# BLE_--_HM-10_--_Carduino_Breakout_v1_0_4.net
KiCad netlist of a schematic drawn in EAGLE
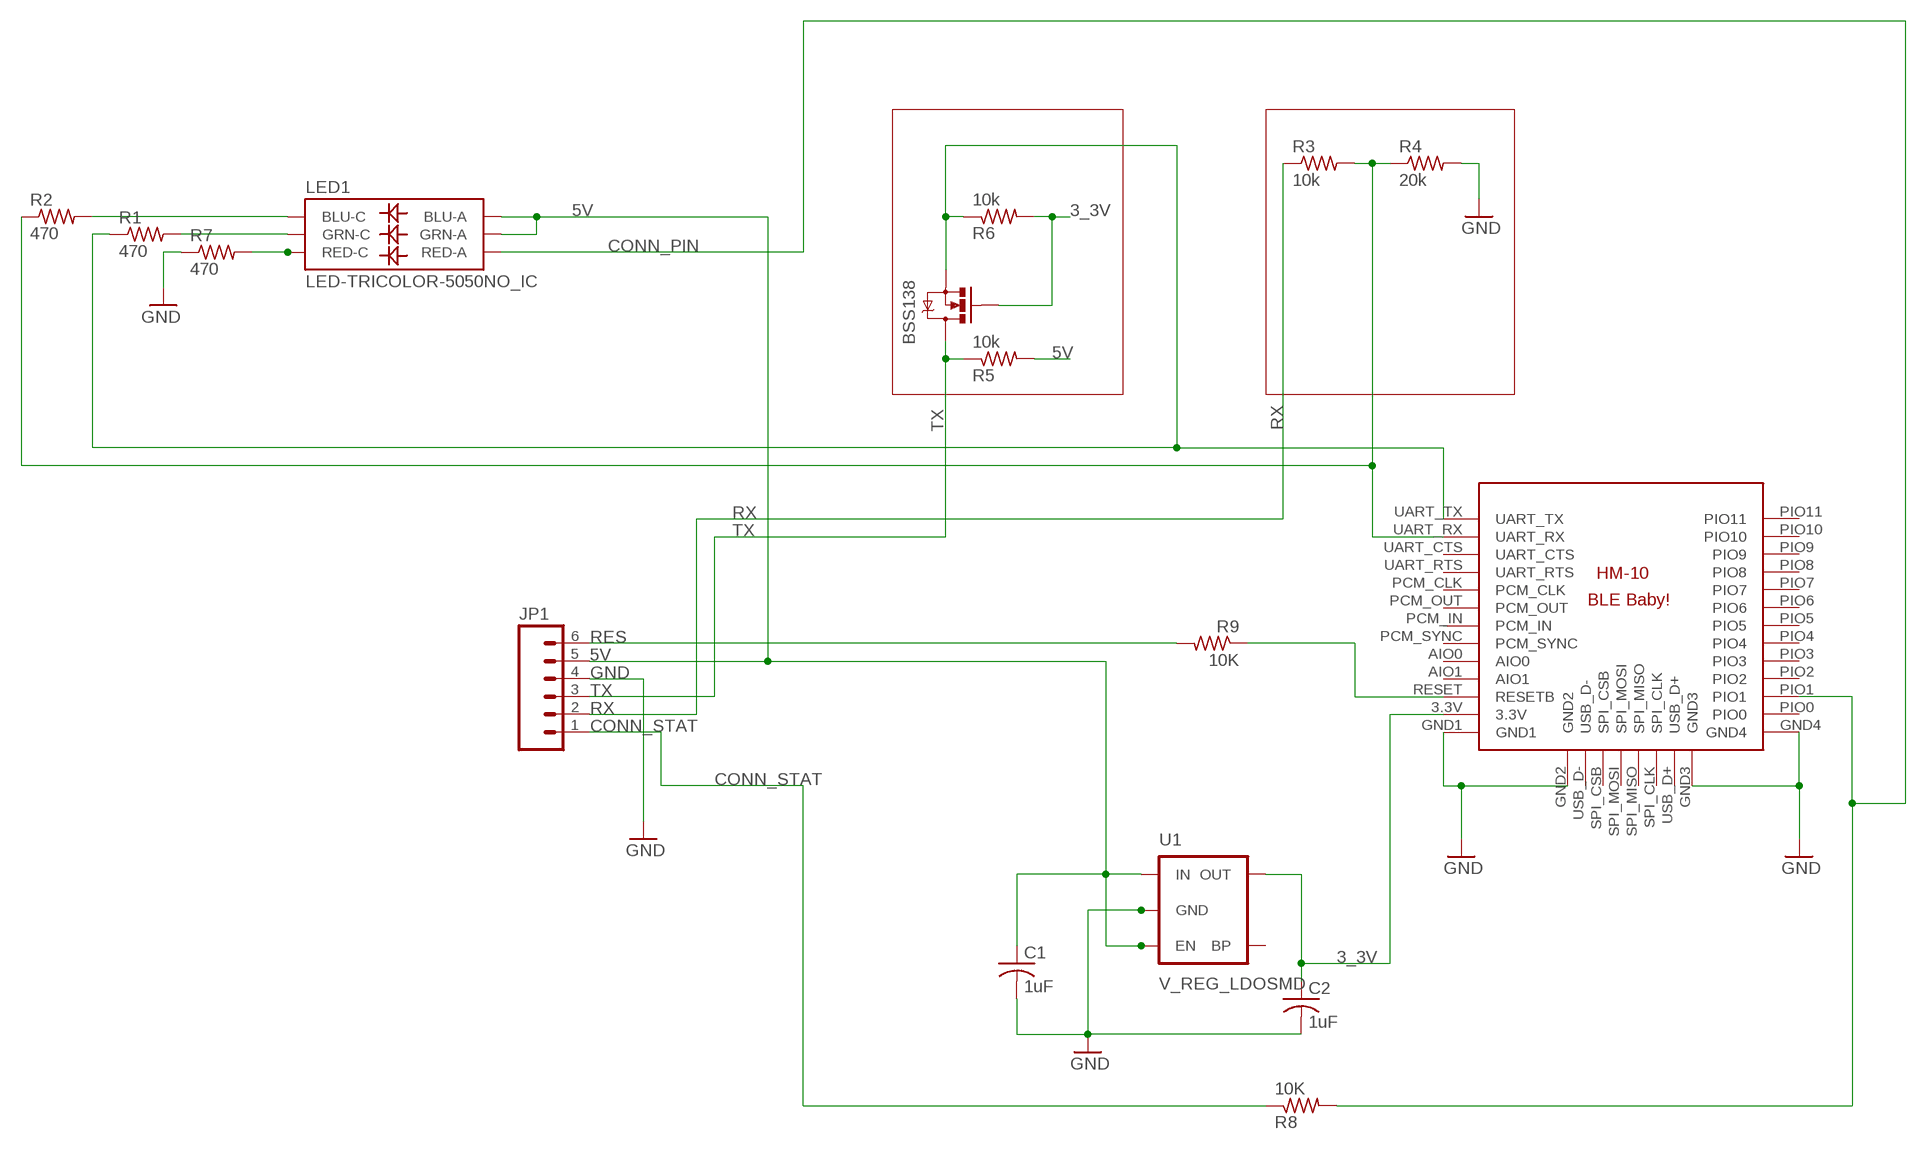
[diagram p0: schematic, sheet 1]

(export (version "E")
  (design (tool "Eeschema 10.0.6"))
  (components
    (comp (ref "BSS138")
      (value "MOSFET-NCHANNELSMD")
      (footprint "eagle-import:SOT23-3")
      (libsource (lib "eagle-import") (part "MOSFET-NCHANNELSMD"))
    )
    (comp (ref "C1")
      (value "1uF")
      (footprint "eagle-import:C0402")
      (libsource (lib "eagle-import") (part "C-USC0402"))
    )
    (comp (ref "C2")
      (value "1uF")
      (footprint "eagle-import:C0402")
      (libsource (lib "eagle-import") (part "C-USC0402"))
    )
    (comp (ref "JP1")
      (value "M06SIP")
      (footprint "eagle-import:1X06")
      (libsource (lib "eagle-import") (part "M06SIP"))
    )
    (comp (ref "LED1")
      (value "LED-TRICOLOR-5050NO_IC")
      (footprint "eagle-import:LED-TRICOLOR-5050")
      (libsource (lib "eagle-import") (part "LED-TRICOLOR-5050NO_IC"))
    )
    (comp (ref "R1")
      (value "470")
      (footprint "eagle-import:R0402")
      (libsource (lib "eagle-import") (part "R-US_R0402"))
    )
    (comp (ref "R2")
      (value "470")
      (footprint "eagle-import:R0402")
      (libsource (lib "eagle-import") (part "R-US_R0402"))
    )
    (comp (ref "R3")
      (value "10k")
      (footprint "eagle-import:R0402")
      (libsource (lib "eagle-import") (part "R-US_R0402"))
    )
    (comp (ref "R4")
      (value "20k")
      (footprint "eagle-import:R0402")
      (libsource (lib "eagle-import") (part "R-US_R0402"))
    )
    (comp (ref "R5")
      (value "10k")
      (footprint "eagle-import:R0402")
      (libsource (lib "eagle-import") (part "R-US_R0402"))
    )
    (comp (ref "R6")
      (value "10k")
      (footprint "eagle-import:R0402")
      (libsource (lib "eagle-import") (part "R-US_R0402"))
    )
    (comp (ref "R7")
      (value "470")
      (footprint "eagle-import:R0402")
      (libsource (lib "eagle-import") (part "R-US_R0402"))
    )
    (comp (ref "R8")
      (value "10K")
      (footprint "eagle-import:R0402")
      (libsource (lib "eagle-import") (part "R-US_R0402"))
    )
    (comp (ref "R9")
      (value "10K")
      (footprint "eagle-import:R0402")
      (libsource (lib "eagle-import") (part "R-US_R0402"))
    )
    (comp (ref "U$1")
      (value "BLE-HM-10")
      (footprint "eagle-import:BLE-HM-10")
      (libsource (lib "eagle-import") (part "BLE-HM-10"))
    )
    (comp (ref "U1")
      (value "V_REG_LDOSMD")
      (footprint "eagle-import:SOT23-5")
      (libsource (lib "eagle-import") (part "V_REG_LDOSMD"))
    )
  )
  (nets
    (net (code "1") (name "/3_3V") (class "Default")
      (node (ref "BSS138") (pin "1") (pinfunction "G_1") (pintype "passive"))
      (node (ref "C2") (pin "1") (pinfunction "1_1") (pintype "passive"))
      (node (ref "R6") (pin "2") (pinfunction "2_2") (pintype "passive"))
      (node (ref "U$1") (pin "3.3V") (pinfunction "3.3V_3.3V") (pintype "bidirectional"))
      (node (ref "U1") (pin "5") (pinfunction "OUT_5") (pintype "passive"))
    )
    (net (code "2") (name "/5V") (class "Default")
      (node (ref "C1") (pin "1") (pinfunction "1_1") (pintype "passive"))
      (node (ref "JP1") (pin "5") (pinfunction "5_5") (pintype "passive"))
      (node (ref "LED1") (pin "1") (pinfunction "GRN-A_1") (pintype "bidirectional"))
      (node (ref "LED1") (pin "3") (pinfunction "BLU-A_3") (pintype "bidirectional"))
      (node (ref "R5") (pin "2") (pinfunction "2_2") (pintype "passive"))
      (node (ref "U1") (pin "1") (pinfunction "IN_1") (pintype "input"))
      (node (ref "U1") (pin "3") (pinfunction "EN_3") (pintype "input"))
    )
    (net (code "3") (name "/CONN_PIN") (class "Default")
      (node (ref "LED1") (pin "2") (pinfunction "RED-A_2") (pintype "bidirectional"))
      (node (ref "R8") (pin "2") (pinfunction "2_2") (pintype "passive"))
      (node (ref "U$1") (pin "PIO1") (pinfunction "PIO1_PIO1") (pintype "bidirectional"))
    )
    (net (code "4") (name "/CONN_STAT") (class "Default")
      (node (ref "JP1") (pin "1") (pinfunction "1_1") (pintype "passive"))
      (node (ref "R8") (pin "1") (pinfunction "1_1") (pintype "passive"))
    )
    (net (code "5") (name "/RES") (class "Default")
      (node (ref "R9") (pin "1") (pinfunction "1_1") (pintype "passive"))
      (node (ref "U$1") (pin "RESET") (pinfunction "RESETB_RESET") (pintype "bidirectional"))
    )
    (net (code "6") (name "/RX") (class "Default")
      (node (ref "JP1") (pin "2") (pinfunction "2_2") (pintype "passive"))
      (node (ref "R3") (pin "1") (pinfunction "1_1") (pintype "passive"))
    )
    (net (code "7") (name "/TX") (class "Default")
      (node (ref "BSS138") (pin "3") (pinfunction "D_3") (pintype "passive"))
      (node (ref "JP1") (pin "3") (pinfunction "3_3") (pintype "passive"))
      (node (ref "R5") (pin "1") (pinfunction "1_1") (pintype "passive"))
    )
    (net (code "8") (name "GND") (class "Default")
      (node (ref "C1") (pin "2") (pinfunction "2_2") (pintype "passive"))
      (node (ref "C2") (pin "2") (pinfunction "2_2") (pintype "passive"))
      (node (ref "JP1") (pin "4") (pinfunction "4_4") (pintype "passive"))
      (node (ref "R4") (pin "2") (pinfunction "2_2") (pintype "passive"))
      (node (ref "R7") (pin "1") (pinfunction "1_1") (pintype "passive"))
      (node (ref "U$1") (pin "GND1") (pinfunction "GND1_GND1") (pintype "bidirectional"))
      (node (ref "U$1") (pin "GND2") (pinfunction "GND2_GND2") (pintype "bidirectional"))
      (node (ref "U$1") (pin "GND3") (pinfunction "GND3_GND3") (pintype "bidirectional"))
      (node (ref "U$1") (pin "GND4") (pinfunction "GND4_GND4") (pintype "bidirectional"))
      (node (ref "U1") (pin "2") (pinfunction "GND_2") (pintype "input"))
    )
    (net (code "9") (name "Net-(BSS138-S)") (class "Default")
      (node (ref "BSS138") (pin "2") (pinfunction "S_2") (pintype "passive"))
      (node (ref "R1") (pin "1") (pinfunction "1_1") (pintype "passive"))
      (node (ref "R6") (pin "1") (pinfunction "1_1") (pintype "passive"))
      (node (ref "U$1") (pin "UART_TX") (pinfunction "UART_TX_UART_TX") (pintype "bidirectional"))
    )
    (net (code "10") (name "Net-(JP1-Pad6)") (class "Default")
      (node (ref "JP1") (pin "6") (pinfunction "6_6") (pintype "passive"))
      (node (ref "R9") (pin "2") (pinfunction "2_2") (pintype "passive"))
    )
    (net (code "11") (name "Net-(LED1-BLU-C)") (class "Default")
      (node (ref "LED1") (pin "4") (pinfunction "BLU-C_4") (pintype "bidirectional"))
      (node (ref "R2") (pin "2") (pinfunction "2_2") (pintype "passive"))
    )
    (net (code "12") (name "Net-(LED1-GRN-C)") (class "Default")
      (node (ref "LED1") (pin "6") (pinfunction "GRN-C_6") (pintype "bidirectional"))
      (node (ref "R1") (pin "2") (pinfunction "2_2") (pintype "passive"))
    )
    (net (code "13") (name "Net-(LED1-RED-C)") (class "Default")
      (node (ref "LED1") (pin "5") (pinfunction "RED-C_5") (pintype "bidirectional"))
      (node (ref "R7") (pin "2") (pinfunction "2_2") (pintype "passive"))
    )
    (net (code "14") (name "Net-(R2-Pad1)") (class "Default")
      (node (ref "R2") (pin "1") (pinfunction "1_1") (pintype "passive"))
      (node (ref "R3") (pin "2") (pinfunction "2_2") (pintype "passive"))
      (node (ref "R4") (pin "1") (pinfunction "1_1") (pintype "passive"))
      (node (ref "U$1") (pin "UART_RX") (pinfunction "UART_RX_UART_RX") (pintype "bidirectional"))
    )
    (net (code "15") (name "unconnected-(U$1-PadAIO0)") (class "Default")
      (node (ref "U$1") (pin "AIO0") (pinfunction "AIO0_AIO0") (pintype "bidirectional"))
    )
    (net (code "16") (name "unconnected-(U$1-PadAIO1)") (class "Default")
      (node (ref "U$1") (pin "AIO1") (pinfunction "AIO1_AIO1") (pintype "bidirectional"))
    )
    (net (code "17") (name "unconnected-(U$1-PadPCM_CLK)") (class "Default")
      (node (ref "U$1") (pin "PCM_CLK") (pinfunction "PCM_CLK_PCM_CLK") (pintype "bidirectional"))
    )
    (net (code "18") (name "unconnected-(U$1-PadPCM_IN)") (class "Default")
      (node (ref "U$1") (pin "PCM_IN") (pinfunction "PCM_IN_PCM_IN") (pintype "bidirectional"))
    )
    (net (code "19") (name "unconnected-(U$1-PadPCM_OUT)") (class "Default")
      (node (ref "U$1") (pin "PCM_OUT") (pinfunction "PCM_OUT_PCM_OUT") (pintype "bidirectional"))
    )
    (net (code "20") (name "unconnected-(U$1-PadPCM_SYNC)") (class "Default")
      (node (ref "U$1") (pin "PCM_SYNC") (pinfunction "PCM_SYNC_PCM_SYNC") (pintype "bidirectional"))
    )
    (net (code "21") (name "unconnected-(U$1-PadPIO0)") (class "Default")
      (node (ref "U$1") (pin "PIO0") (pinfunction "PIO0_PIO0") (pintype "bidirectional"))
    )
    (net (code "22") (name "unconnected-(U$1-PadPIO2)") (class "Default")
      (node (ref "U$1") (pin "PIO2") (pinfunction "PIO2_PIO2") (pintype "bidirectional"))
    )
    (net (code "23") (name "unconnected-(U$1-PadPIO3)") (class "Default")
      (node (ref "U$1") (pin "PIO3") (pinfunction "PIO3_PIO3") (pintype "bidirectional"))
    )
    (net (code "24") (name "unconnected-(U$1-PadPIO4)") (class "Default")
      (node (ref "U$1") (pin "PIO4") (pinfunction "PIO4_PIO4") (pintype "bidirectional"))
    )
    (net (code "25") (name "unconnected-(U$1-PadPIO5)") (class "Default")
      (node (ref "U$1") (pin "PIO5") (pinfunction "PIO5_PIO5") (pintype "bidirectional"))
    )
    (net (code "26") (name "unconnected-(U$1-PadPIO6)") (class "Default")
      (node (ref "U$1") (pin "PIO6") (pinfunction "PIO6_PIO6") (pintype "bidirectional"))
    )
    (net (code "27") (name "unconnected-(U$1-PadPIO7)") (class "Default")
      (node (ref "U$1") (pin "PIO7") (pinfunction "PIO7_PIO7") (pintype "bidirectional"))
    )
    (net (code "28") (name "unconnected-(U$1-PadPIO8)") (class "Default")
      (node (ref "U$1") (pin "PIO8") (pinfunction "PIO8_PIO8") (pintype "bidirectional"))
    )
    (net (code "29") (name "unconnected-(U$1-PadPIO9)") (class "Default")
      (node (ref "U$1") (pin "PIO9") (pinfunction "PIO9_PIO9") (pintype "bidirectional"))
    )
    (net (code "30") (name "unconnected-(U$1-PadPIO10)") (class "Default")
      (node (ref "U$1") (pin "PIO10") (pinfunction "PIO10_PIO10") (pintype "bidirectional"))
    )
    (net (code "31") (name "unconnected-(U$1-PadPIO11)") (class "Default")
      (node (ref "U$1") (pin "PIO11") (pinfunction "PIO11_PIO11") (pintype "bidirectional"))
    )
    (net (code "32") (name "unconnected-(U$1-PadSPI_CLK)") (class "Default")
      (node (ref "U$1") (pin "SPI_CLK") (pinfunction "SPI_CLK_SPI_CLK") (pintype "bidirectional"))
    )
    (net (code "33") (name "unconnected-(U$1-PadSPI_CSB)") (class "Default")
      (node (ref "U$1") (pin "SPI_CSB") (pinfunction "SPI_CSB_SPI_CSB") (pintype "bidirectional"))
    )
    (net (code "34") (name "unconnected-(U$1-PadSPI_MISO)") (class "Default")
      (node (ref "U$1") (pin "SPI_MISO") (pinfunction "SPI_MISO_SPI_MISO") (pintype "bidirectional"))
    )
    (net (code "35") (name "unconnected-(U$1-PadSPI_MOSI)") (class "Default")
      (node (ref "U$1") (pin "SPI_MOSI") (pinfunction "SPI_MOSI_SPI_MOSI") (pintype "bidirectional"))
    )
    (net (code "36") (name "unconnected-(U$1-PadUART_CTS)") (class "Default")
      (node (ref "U$1") (pin "UART_CTS") (pinfunction "UART_CTS_UART_CTS") (pintype "bidirectional"))
    )
    (net (code "37") (name "unconnected-(U$1-PadUART_RTS)") (class "Default")
      (node (ref "U$1") (pin "UART_RTS") (pinfunction "UART_RTS_UART_RTS") (pintype "bidirectional"))
    )
    (net (code "38") (name "unconnected-(U$1-PadUSB_D+)") (class "Default")
      (node (ref "U$1") (pin "USB_D+") (pinfunction "USB_D+_USB_D+") (pintype "bidirectional"))
    )
    (net (code "39") (name "unconnected-(U$1-PadUSB_D-)") (class "Default")
      (node (ref "U$1") (pin "USB_D-") (pinfunction "USB_D-_USB_D-") (pintype "bidirectional"))
    )
    (net (code "40") (name "unconnected-(U1-BP-Pad4)") (class "Default")
      (node (ref "U1") (pin "4") (pinfunction "BP_4") (pintype "input"))
    )
  )
)
